# simplePDschematicsv3_AZ_SMD.net
KiCad netlist of a schematic drawn in EAGLE
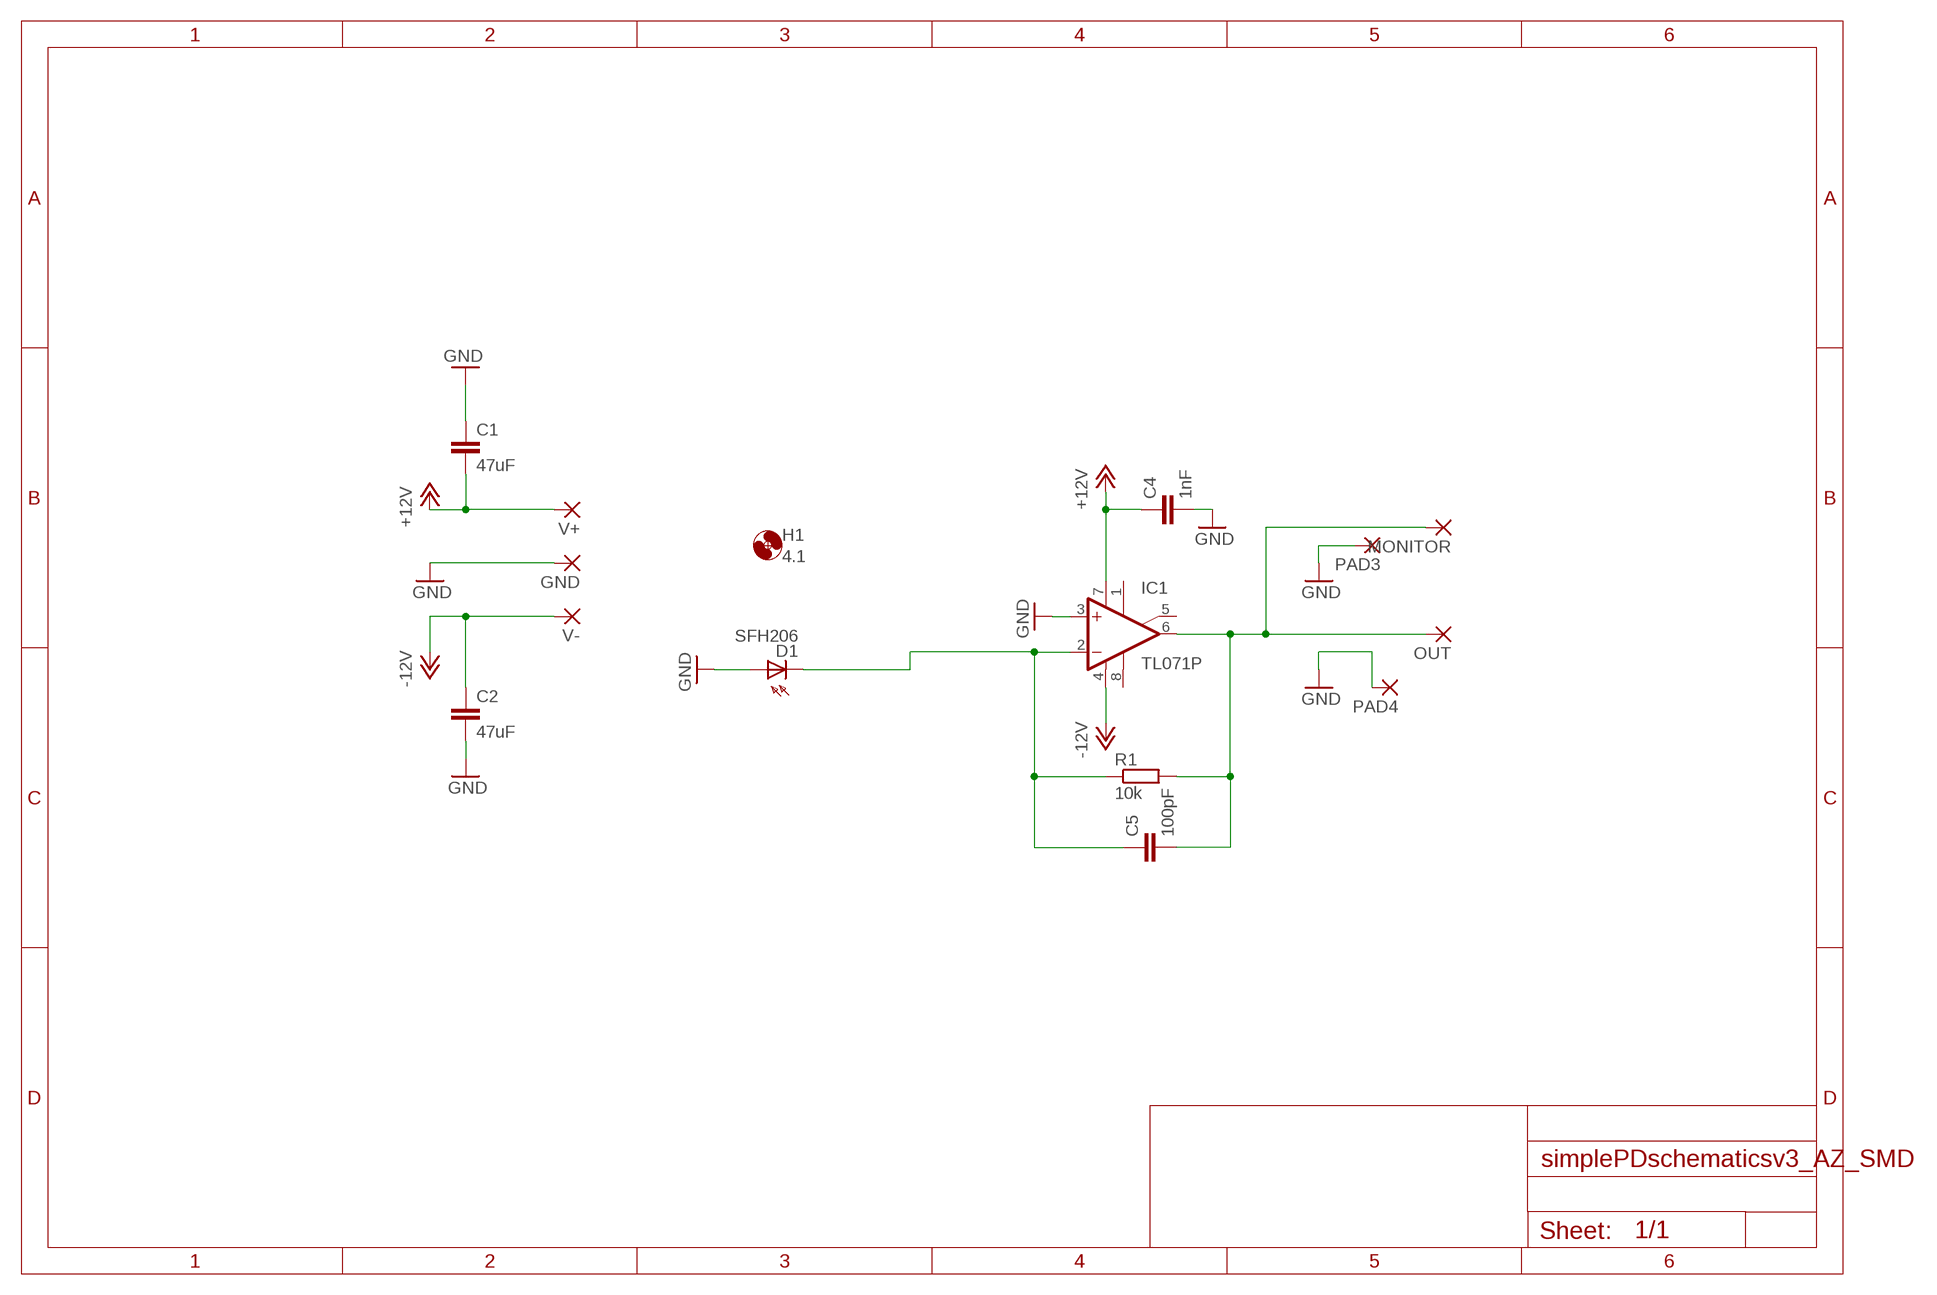
[diagram p0: schematic, sheet 1]

(export (version "E")
  (design (tool "Eeschema 10.0.6"))
  (components
    (comp (ref "C1")
      (value "47uF")
      (footprint "eagle-import:C050-075X075")
      (libsource (lib "eagle-import") (part "C-EU050-075X075"))
    )
    (comp (ref "C2")
      (value "47uF")
      (footprint "eagle-import:C050-075X075")
      (libsource (lib "eagle-import") (part "C-EU050-075X075"))
    )
    (comp (ref "C4")
      (value "1nF")
      (footprint "eagle-import:C025-050X050")
      (libsource (lib "eagle-import") (part "C-EU025-050X050"))
    )
    (comp (ref "C5")
      (value "100pF")
      (footprint "eagle-import:C025-050X050")
      (libsource (lib "eagle-import") (part "C-EU025-050X050"))
    )
    (comp (ref "D1")
      (value "SFH206")
      (footprint "eagle-import:SFH206")
      (fields (field (name "MPN") "SFH206K"))
      (libsource (lib "eagle-import") (part "SFH206"))
    )
    (comp (ref "GND")
      (value "1,6/0,9")
      (footprint "eagle-import:1,6_0,9")
      (libsource (lib "eagle-import") (part "1,6/0,9"))
    )
    (comp (ref "H1")
      (value "4.1")
      (footprint "eagle-import:4,1")
      (libsource (lib "eagle-import") (part "MOUNT-HOLE4.1"))
    )
    (comp (ref "IC1")
      (value "TL071P")
      (footprint "eagle-import:DIL08")
      (libsource (lib "eagle-import") (part "TL071P"))
    )
    (comp (ref "MONITOR")
      (value "1,6/0,9")
      (footprint "eagle-import:1,6_0,9")
      (libsource (lib "eagle-import") (part "1,6/0,9"))
    )
    (comp (ref "OUT")
      (value "1,6/0,9")
      (footprint "eagle-import:1,6_0,9")
      (libsource (lib "eagle-import") (part "1,6/0,9"))
    )
    (comp (ref "PAD3")
      (value "1,6/0,9")
      (footprint "eagle-import:1,6_0,9")
      (libsource (lib "eagle-import") (part "1,6/0,9"))
    )
    (comp (ref "PAD4")
      (value "1,6/0,9")
      (footprint "eagle-import:1,6_0,9")
      (libsource (lib "eagle-import") (part "1,6/0,9"))
    )
    (comp (ref "R1")
      (value "10k")
      (footprint "eagle-import:M1206")
      (libsource (lib "eagle-import") (part "R-EU_M1206"))
    )
    (comp (ref "V+")
      (value "1,6/0,9")
      (footprint "eagle-import:1,6_0,9")
      (libsource (lib "eagle-import") (part "1,6/0,9"))
    )
    (comp (ref "V-")
      (value "1,6/0,9")
      (footprint "eagle-import:1,6_0,9")
      (libsource (lib "eagle-import") (part "1,6/0,9"))
    )
  )
  (nets
    (net (code "1") (name "+12V") (class "Default")
      (node (ref "C1") (pin "2") (pinfunction "2_2") (pintype "passive"))
      (node (ref "C4") (pin "1") (pinfunction "1_1") (pintype "passive"))
      (node (ref "IC1") (pin "7") (pinfunction "V+_7") (pintype "power_in"))
      (node (ref "V+") (pin "1") (pinfunction "P_1") (pintype "passive"))
    )
    (net (code "2") (name "-12V") (class "Default")
      (node (ref "C2") (pin "1") (pinfunction "1_1") (pintype "passive"))
      (node (ref "IC1") (pin "4") (pinfunction "V-_4") (pintype "power_in"))
      (node (ref "V-") (pin "1") (pinfunction "P_1") (pintype "passive"))
    )
    (net (code "3") (name "GND") (class "Default")
      (node (ref "C1") (pin "1") (pinfunction "1_1") (pintype "passive"))
      (node (ref "C2") (pin "2") (pinfunction "2_2") (pintype "passive"))
      (node (ref "C4") (pin "2") (pinfunction "2_2") (pintype "passive"))
      (node (ref "D1") (pin "A") (pinfunction "A_A") (pintype "passive"))
      (node (ref "GND") (pin "1") (pinfunction "P_1") (pintype "passive"))
      (node (ref "IC1") (pin "3") (pinfunction "+IN_3") (pintype "input"))
      (node (ref "PAD3") (pin "1") (pinfunction "P_1") (pintype "passive"))
      (node (ref "PAD4") (pin "1") (pinfunction "P_1") (pintype "passive"))
    )
    (net (code "4") (name "Net-(D1-C)") (class "Default")
      (node (ref "C5") (pin "1") (pinfunction "1_1") (pintype "passive"))
      (node (ref "D1") (pin "K") (pinfunction "C_K") (pintype "passive"))
      (node (ref "IC1") (pin "2") (pinfunction "-IN_2") (pintype "input"))
      (node (ref "R1") (pin "1") (pinfunction "1_1") (pintype "passive"))
    )
    (net (code "5") (name "Net-(IC1-OUT)") (class "Default")
      (node (ref "C5") (pin "2") (pinfunction "2_2") (pintype "passive"))
      (node (ref "IC1") (pin "6") (pinfunction "OUT_6") (pintype "output"))
      (node (ref "MONITOR") (pin "1") (pinfunction "P_1") (pintype "passive"))
      (node (ref "OUT") (pin "1") (pinfunction "P_1") (pintype "passive"))
      (node (ref "R1") (pin "2") (pinfunction "2_2") (pintype "passive"))
    )
    (net (code "6") (name "unconnected-(IC1-ON1-Pad1)") (class "Default")
      (node (ref "IC1") (pin "1") (pinfunction "ON1_1") (pintype "passive"))
    )
    (net (code "7") (name "unconnected-(IC1-ON2-Pad5)") (class "Default")
      (node (ref "IC1") (pin "5") (pinfunction "ON2_5") (pintype "passive"))
    )
    (net (code "8") (name "unconnected-(IC1-OPT-Pad8)") (class "Default")
      (node (ref "IC1") (pin "8") (pinfunction "OPT_8") (pintype "passive"))
    )
  )
)
